# piezo-preamp-alex-rice-FETS_v4_9V.net
KiCad netlist of a schematic drawn in EAGLE
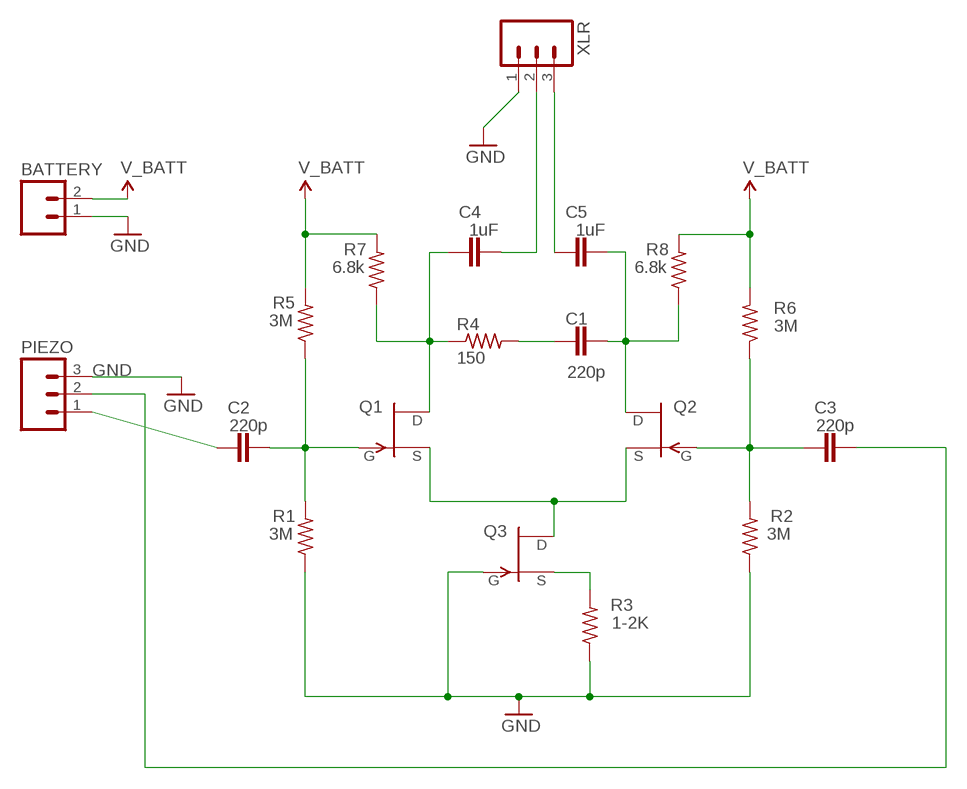
[diagram p0: schematic, sheet 1]

(export (version "E")
  (design (tool "Eeschema 10.0.6"))
  (components
    (comp (ref "BATTERY")
      (value "M02PTH")
      (footprint "eagle-import:1X02")
      (libsource (lib "eagle-import") (part "M02PTH"))
    )
    (comp (ref "C1")
      (value "220p")
      (footprint "eagle-import:C050-030X075")
      (libsource (lib "eagle-import") (part "C-EU050-030X075"))
    )
    (comp (ref "C2")
      (value "220p")
      (footprint "eagle-import:C050-030X075")
      (libsource (lib "eagle-import") (part "C-EU050-030X075"))
    )
    (comp (ref "C3")
      (value "220p")
      (footprint "eagle-import:C050-030X075")
      (libsource (lib "eagle-import") (part "C-EU050-030X075"))
    )
    (comp (ref "C4")
      (value "1uF")
      (footprint "eagle-import:C050-030X075")
      (libsource (lib "eagle-import") (part "C-EU050-030X075"))
    )
    (comp (ref "C5")
      (value "1uF")
      (footprint "eagle-import:C050-030X075")
      (libsource (lib "eagle-import") (part "C-EU050-030X075"))
    )
    (comp (ref "PIEZO")
      (value "M03PTH")
      (footprint "eagle-import:1X03")
      (libsource (lib "eagle-import") (part "M03PTH"))
    )
    (comp (ref "Q1")
      (value "2N3819")
      (footprint "eagle-import:TO92")
      (libsource (lib "eagle-import") (part "2N3819-WIDETO92_WIDE"))
    )
    (comp (ref "Q2")
      (value "2N3819-WIDETO92_WIDE")
      (footprint "eagle-import:TO92")
      (libsource (lib "eagle-import") (part "2N3819-WIDETO92_WIDE"))
    )
    (comp (ref "Q3")
      (value "2N3819-WIDETO92_WIDE")
      (footprint "eagle-import:TO92")
      (libsource (lib "eagle-import") (part "2N3819-WIDETO92_WIDE"))
    )
    (comp (ref "R1")
      (value "3M")
      (footprint "eagle-import:0204_5")
      (libsource (lib "eagle-import") (part "R-US_0204/5"))
    )
    (comp (ref "R2")
      (value "3M")
      (footprint "eagle-import:0204_5")
      (libsource (lib "eagle-import") (part "R-US_0204/5"))
    )
    (comp (ref "R3")
      (value "1-2K")
      (footprint "eagle-import:0204_5")
      (libsource (lib "eagle-import") (part "R-US_0204/5"))
    )
    (comp (ref "R4")
      (value "150")
      (footprint "eagle-import:0204_5")
      (libsource (lib "eagle-import") (part "resistor_R-US_0204/5"))
    )
    (comp (ref "R5")
      (value "3M")
      (footprint "eagle-import:0204_5")
      (libsource (lib "eagle-import") (part "R-US_0204/5"))
    )
    (comp (ref "R6")
      (value "3M")
      (footprint "eagle-import:0204_5")
      (libsource (lib "eagle-import") (part "R-US_0204/5"))
    )
    (comp (ref "R7")
      (value "6.8k")
      (footprint "eagle-import:0204_5")
      (libsource (lib "eagle-import") (part "R-US_0204/5"))
    )
    (comp (ref "R8")
      (value "6.8k")
      (footprint "eagle-import:0204_5")
      (libsource (lib "eagle-import") (part "R-US_0204/5"))
    )
    (comp (ref "XLR")
      (value "M03PTH")
      (footprint "eagle-import:1X03")
      (libsource (lib "eagle-import") (part "M03PTH"))
    )
  )
  (nets
    (net (code "1") (name "GND") (class "Default")
      (node (ref "BATTERY") (pin "1") (pinfunction "1_1") (pintype "passive"))
      (node (ref "PIEZO") (pin "3") (pinfunction "3_3") (pintype "passive"))
      (node (ref "Q3") (pin "2") (pinfunction "G_2") (pintype "passive"))
      (node (ref "R1") (pin "1") (pinfunction "1_1") (pintype "passive"))
      (node (ref "R2") (pin "1") (pinfunction "1_1") (pintype "passive"))
      (node (ref "R3") (pin "1") (pinfunction "1_1") (pintype "passive"))
      (node (ref "XLR") (pin "1") (pinfunction "1_1") (pintype "passive"))
    )
    (net (code "2") (name "Net-(C1-Pad1)") (class "Default")
      (node (ref "C1") (pin "1") (pinfunction "1_1") (pintype "passive"))
      (node (ref "R4") (pin "2") (pinfunction "2_2") (pintype "passive"))
    )
    (net (code "3") (name "Net-(C2-Pad1)") (class "Default")
      (node (ref "C2") (pin "1") (pinfunction "1_1") (pintype "passive"))
      (node (ref "PIEZO") (pin "1") (pinfunction "1_1") (pintype "passive"))
    )
    (net (code "4") (name "Net-(C3-Pad2)") (class "Default")
      (node (ref "C3") (pin "2") (pinfunction "2_2") (pintype "passive"))
      (node (ref "PIEZO") (pin "2") (pinfunction "2_2") (pintype "passive"))
    )
    (net (code "5") (name "Net-(C4-Pad2)") (class "Default")
      (node (ref "C4") (pin "2") (pinfunction "2_2") (pintype "passive"))
      (node (ref "XLR") (pin "2") (pinfunction "2_2") (pintype "passive"))
    )
    (net (code "6") (name "Net-(C5-Pad1)") (class "Default")
      (node (ref "C5") (pin "1") (pinfunction "1_1") (pintype "passive"))
      (node (ref "XLR") (pin "3") (pinfunction "3_3") (pintype "passive"))
    )
    (net (code "7") (name "Net-(Q1-D)") (class "Default")
      (node (ref "C4") (pin "1") (pinfunction "1_1") (pintype "passive"))
      (node (ref "Q1") (pin "1") (pinfunction "D_1") (pintype "passive"))
      (node (ref "R4") (pin "1") (pinfunction "1_1") (pintype "passive"))
      (node (ref "R7") (pin "1") (pinfunction "1_1") (pintype "passive"))
    )
    (net (code "8") (name "Net-(Q1-G)") (class "Default")
      (node (ref "C2") (pin "2") (pinfunction "2_2") (pintype "passive"))
      (node (ref "Q1") (pin "2") (pinfunction "G_2") (pintype "passive"))
      (node (ref "R1") (pin "2") (pinfunction "2_2") (pintype "passive"))
      (node (ref "R5") (pin "1") (pinfunction "1_1") (pintype "passive"))
    )
    (net (code "9") (name "Net-(Q1-S)") (class "Default")
      (node (ref "Q1") (pin "3") (pinfunction "S_3") (pintype "passive"))
      (node (ref "Q2") (pin "3") (pinfunction "S_3") (pintype "passive"))
      (node (ref "Q3") (pin "1") (pinfunction "D_1") (pintype "passive"))
    )
    (net (code "10") (name "Net-(Q2-D)") (class "Default")
      (node (ref "C1") (pin "2") (pinfunction "2_2") (pintype "passive"))
      (node (ref "C5") (pin "2") (pinfunction "2_2") (pintype "passive"))
      (node (ref "Q2") (pin "1") (pinfunction "D_1") (pintype "passive"))
      (node (ref "R8") (pin "1") (pinfunction "1_1") (pintype "passive"))
    )
    (net (code "11") (name "Net-(Q2-G)") (class "Default")
      (node (ref "C3") (pin "1") (pinfunction "1_1") (pintype "passive"))
      (node (ref "Q2") (pin "2") (pinfunction "G_2") (pintype "passive"))
      (node (ref "R2") (pin "2") (pinfunction "2_2") (pintype "passive"))
      (node (ref "R6") (pin "1") (pinfunction "1_1") (pintype "passive"))
    )
    (net (code "12") (name "Net-(Q3-S)") (class "Default")
      (node (ref "Q3") (pin "3") (pinfunction "S_3") (pintype "passive"))
      (node (ref "R3") (pin "2") (pinfunction "2_2") (pintype "passive"))
    )
    (net (code "13") (name "V_BATT") (class "Default")
      (node (ref "BATTERY") (pin "2") (pinfunction "2_2") (pintype "passive"))
      (node (ref "R5") (pin "2") (pinfunction "2_2") (pintype "passive"))
      (node (ref "R6") (pin "2") (pinfunction "2_2") (pintype "passive"))
      (node (ref "R7") (pin "2") (pinfunction "2_2") (pintype "passive"))
      (node (ref "R8") (pin "2") (pinfunction "2_2") (pintype "passive"))
    )
  )
)
